# 467444_130_3_5-R1.net
KiCad netlist of a schematic drawn in Altium Designer
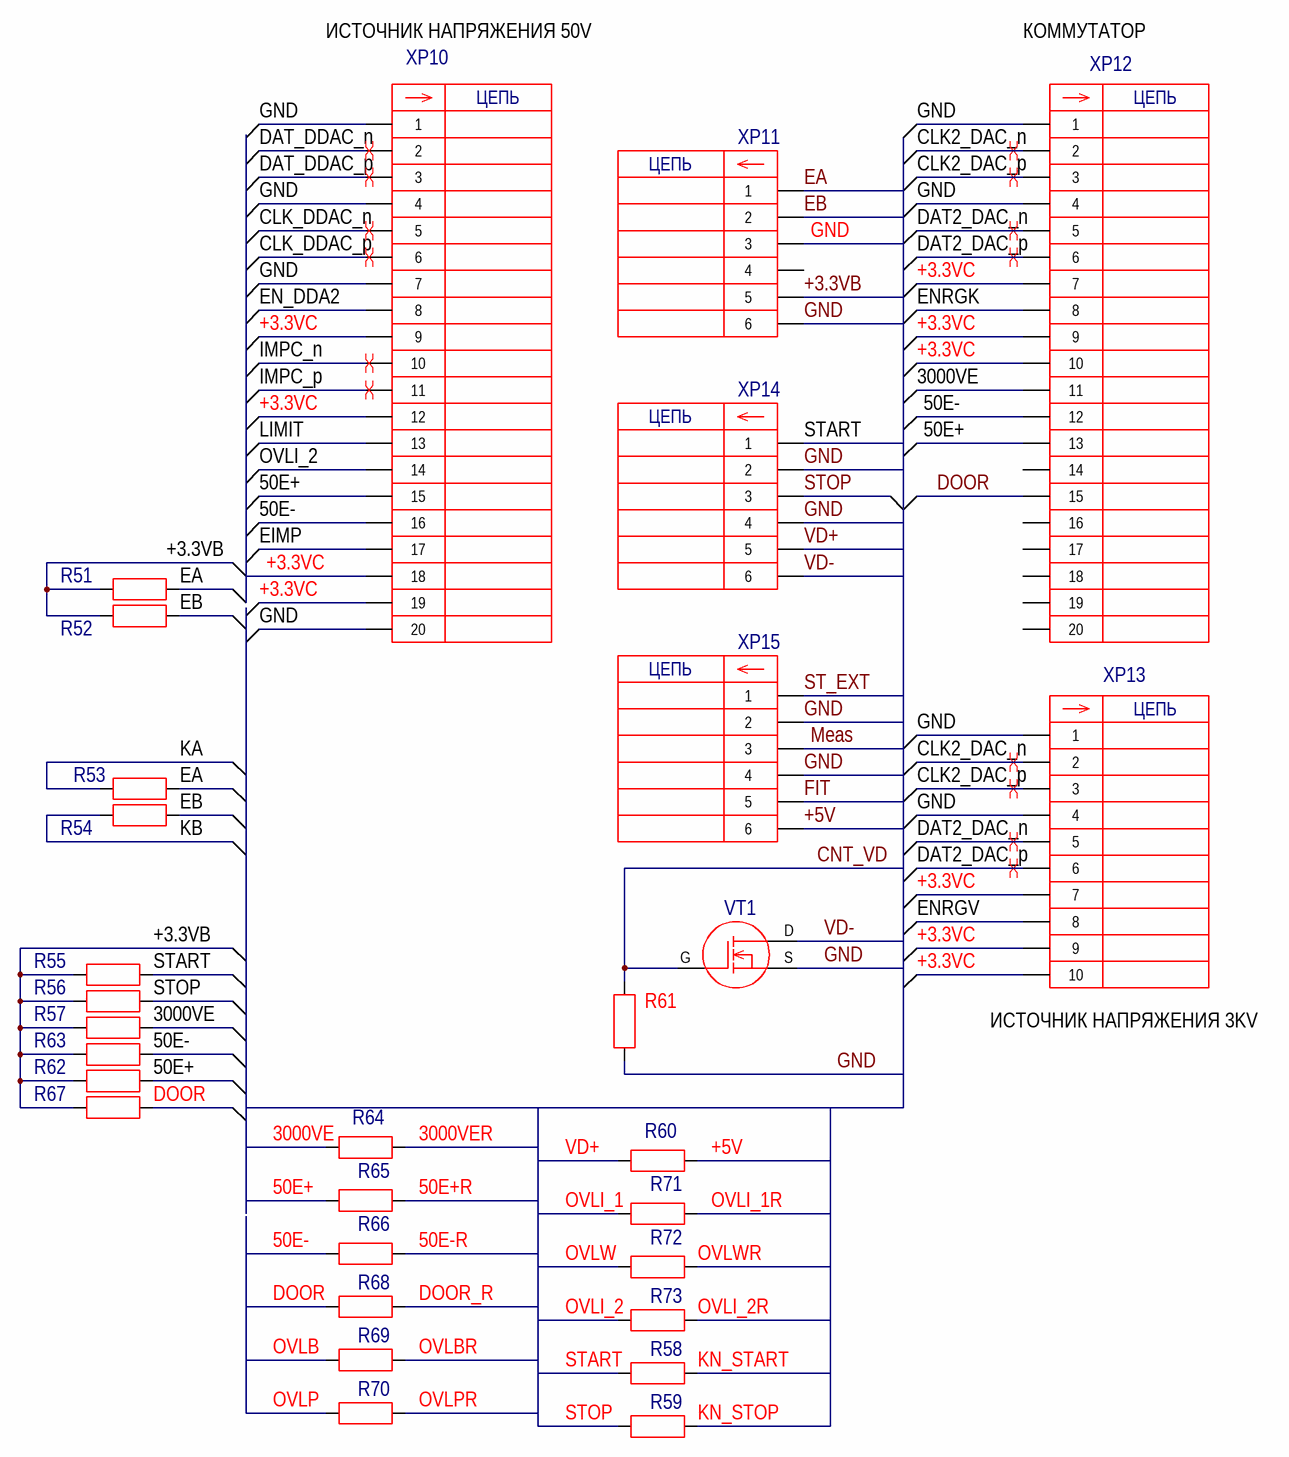
[diagram p0: УШЯИ.467444.130Э3_5-R1.SchDoc]

(export (version "E")
  (design (tool "Eeschema 10.0.6"))
  (components
    (comp (ref "R51")
      (value "5,1k")
      (footprint "R_0805 [2012 Metric]")
      (fields (field (name "TOLERANCE") "±5%"))
      (libsource (lib "lib") (part "R_Const"))
    )
    (comp (ref "R52")
      (value "5,1k")
      (footprint "R_0805 [2012 Metric]")
      (fields (field (name "TOLERANCE") "±5%"))
      (libsource (lib "lib") (part "R_Const"))
    )
    (comp (ref "R53")
      (value "1k")
      (footprint "R_0805 [2012 Metric]")
      (fields (field (name "TOLERANCE") "±5%"))
      (libsource (lib "lib") (part "R_Const"))
    )
    (comp (ref "R54")
      (value "1k")
      (footprint "R_0805 [2012 Metric]")
      (fields (field (name "TOLERANCE") "±5%"))
      (libsource (lib "lib") (part "R_Const"))
    )
    (comp (ref "R55")
      (value "5,1k")
      (footprint "R_0805 [2012 Metric]")
      (fields (field (name "TOLERANCE") "±5%"))
      (libsource (lib "lib") (part "R_Const"))
    )
    (comp (ref "R56")
      (value "5,1k")
      (footprint "R_0805 [2012 Metric]")
      (fields (field (name "TOLERANCE") "±5%"))
      (libsource (lib "lib") (part "R_Const"))
    )
    (comp (ref "R57")
      (value "10k")
      (footprint "R_0805 [2012 Metric]")
      (fields (field (name "TOLERANCE") "±1%"))
      (libsource (lib "lib") (part "R_Const"))
    )
    (comp (ref "R58")
      (value "~")
      (footprint "R_0805 [2012 Metric]")
      (fields (field (name "TOLERANCE") "±5%"))
      (libsource (lib "lib") (part "R_Const"))
    )
    (comp (ref "R59")
      (value "~")
      (footprint "R_0805 [2012 Metric]")
      (fields (field (name "TOLERANCE") "±5%"))
      (libsource (lib "lib") (part "R_Const"))
    )
    (comp (ref "R60")
      (value "150R")
      (footprint "R_0805 [2012 Metric]")
      (fields (field (name "TOLERANCE") "±5%"))
      (libsource (lib "lib") (part "R_Const"))
    )
    (comp (ref "R61")
      (value "10k")
      (footprint "R_0805 [2012 Metric]")
      (fields (field (name "TOLERANCE") "±5%"))
      (libsource (lib "lib") (part "R_Const"))
    )
    (comp (ref "R62")
      (value "3,6k")
      (footprint "R_0805 [2012 Metric]")
      (fields (field (name "TOLERANCE") "±5%"))
      (libsource (lib "lib") (part "R_Const"))
    )
    (comp (ref "R63")
      (value "3,6k")
      (footprint "R_0805 [2012 Metric]")
      (fields (field (name "TOLERANCE") "±5%"))
      (libsource (lib "lib") (part "R_Const"))
    )
    (comp (ref "R64")
      (value "1k")
      (footprint "R_0805 [2012 Metric]")
      (fields (field (name "TOLERANCE") "±5%"))
      (libsource (lib "lib") (part "R_Const"))
    )
    (comp (ref "R65")
      (value "1k")
      (footprint "R_0805 [2012 Metric]")
      (fields (field (name "TOLERANCE") "±5%"))
      (libsource (lib "lib") (part "R_Const"))
    )
    (comp (ref "R66")
      (value "1k")
      (footprint "R_0805 [2012 Metric]")
      (fields (field (name "TOLERANCE") "±5%"))
      (libsource (lib "lib") (part "R_Const"))
    )
    (comp (ref "R67")
      (value "1k")
      (footprint "R_0805 [2012 Metric]")
      (fields (field (name "TOLERANCE") "±5%"))
      (libsource (lib "lib") (part "R_Const"))
    )
    (comp (ref "R68")
      (value "1k")
      (footprint "R_0805 [2012 Metric]")
      (fields (field (name "TOLERANCE") "±5%"))
      (libsource (lib "lib") (part "R_Const"))
    )
    (comp (ref "R69")
      (value "1k")
      (footprint "R_0805 [2012 Metric]")
      (fields (field (name "TOLERANCE") "±5%"))
      (libsource (lib "lib") (part "R_Const"))
    )
    (comp (ref "R70")
      (value "1k")
      (footprint "R_0805 [2012 Metric]")
      (fields (field (name "TOLERANCE") "±5%"))
      (libsource (lib "lib") (part "R_Const"))
    )
    (comp (ref "R71")
      (value "1k")
      (footprint "R_0805 [2012 Metric]")
      (fields (field (name "TOLERANCE") "±5%"))
      (libsource (lib "lib") (part "R_Const"))
    )
    (comp (ref "R72")
      (value "1k")
      (footprint "R_0805 [2012 Metric]")
      (fields (field (name "TOLERANCE") "±5%"))
      (libsource (lib "lib") (part "R_Const"))
    )
    (comp (ref "R73")
      (value "1k")
      (footprint "R_0805 [2012 Metric]")
      (fields (field (name "TOLERANCE") "±5%"))
      (libsource (lib "lib") (part "R_Const"))
    )
    (comp (ref "VT1")
      (value "NDS7002A")
      (footprint "SOT-23-3_[TO-236AB]_Transistor_n")
      (description "Транзистор n-канальный, изолированный затвор")
      (fields (field (name "MANUFACTURER") "Onsemi"))
      (libsource (lib "lib") (part "n-channel"))
    )
    (comp (ref "XP10")
      (value "BH2-20R")
      (footprint "BH2-20R")
      (description "Male, 20 pins, 2 rows, Right Angle, DS1014-20RF1B-B, 2 mm")
      (fields (field (name "MANUFACTURER") "Connfly electronic"))
      (libsource (lib "lib") (part "M_20"))
    )
    (comp (ref "XP11")
      (value "AMPMODU II 280372-2")
      (footprint "AMP II-280372-2")
      (description "Male, 6 pin, 1 row, Vertical, Board-to-Board, 2.54 mm")
      (fields (field (name "MANUFACTURER") "TE Connectivity"))
      (libsource (lib "lib") (part "M_6"))
    )
    (comp (ref "XP12")
      (value "BH2-20R")
      (footprint "BH2-20R")
      (description "Male, 20 pins, 2 rows, Right Angle, DS1014-20RF1B-B, 2 mm")
      (fields (field (name "MANUFACTURER") "Connfly electronic"))
      (libsource (lib "lib") (part "M_20"))
    )
    (comp (ref "XP13")
      (value "BH2-10R")
      (footprint "BH2-10R")
      (description "Male, 10 pins, 2 rows, Vertical, DS1014-10RF1B-B, 2 mm")
      (fields (field (name "MANUFACTURER") "Connfly electronic"))
      (libsource (lib "lib") (part "M_10"))
    )
    (comp (ref "XP14")
      (value "AMPMODU II 280372-2")
      (footprint "AMP II-280372-2")
      (description "Male, 6 pin, 1 row, Vertical, Board-to-Board, 2.54 mm")
      (fields (field (name "MANUFACTURER") "TE Connectivity"))
      (libsource (lib "lib") (part "M_6"))
    )
    (comp (ref "XP15")
      (value "AMPMODU II 280372-2")
      (footprint "AMP II-280372-2")
      (description "Male, 6 pin, 1 row, Vertical, Board-to-Board, 2.54 mm")
      (fields (field (name "MANUFACTURER") "TE Connectivity"))
      (libsource (lib "lib") (part "M_6"))
    )
  )
  (nets
    (net (code "1") (name "/+3.3VB") (class "Default")
      (node (ref "R51") (pin "1") (pinfunction "1_1") (pintype "passive"))
      (node (ref "R52") (pin "1") (pinfunction "1_1") (pintype "passive"))
      (node (ref "R55") (pin "1") (pinfunction "1_1") (pintype "passive"))
      (node (ref "R56") (pin "1") (pinfunction "1_1") (pintype "passive"))
      (node (ref "R57") (pin "1") (pinfunction "1_1") (pintype "passive"))
      (node (ref "R62") (pin "1") (pinfunction "1_1") (pintype "passive"))
      (node (ref "R63") (pin "1") (pinfunction "1_1") (pintype "passive"))
      (node (ref "R67") (pin "1") (pinfunction "1_1") (pintype "passive"))
      (node (ref "XP11") (pin "5") (pinfunction "5_5") (pintype "passive"))
    )
    (net (code "2") (name "/+3.3VC") (class "Default")
      (node (ref "XP10") (pin "12") (pinfunction "12_12") (pintype "passive"))
      (node (ref "XP10") (pin "18") (pinfunction "18_18") (pintype "passive"))
      (node (ref "XP10") (pin "19") (pinfunction "19_19") (pintype "passive"))
      (node (ref "XP10") (pin "9") (pinfunction "9_9") (pintype "passive"))
      (node (ref "XP12") (pin "10") (pinfunction "10_10") (pintype "passive"))
      (node (ref "XP12") (pin "7") (pinfunction "7_7") (pintype "passive"))
      (node (ref "XP12") (pin "9") (pinfunction "9_9") (pintype "passive"))
      (node (ref "XP13") (pin "10") (pinfunction "10_10") (pintype "passive"))
      (node (ref "XP13") (pin "7") (pinfunction "7_7") (pintype "passive"))
      (node (ref "XP13") (pin "9") (pinfunction "9_9") (pintype "passive"))
    )
    (net (code "3") (name "/+5V") (class "Default")
      (node (ref "R60") (pin "2") (pinfunction "2_2") (pintype "passive"))
      (node (ref "XP15") (pin "6") (pinfunction "6_6") (pintype "passive"))
    )
    (net (code "4") (name "/50E+") (class "Default")
      (node (ref "R62") (pin "2") (pinfunction "2_2") (pintype "passive"))
      (node (ref "R65") (pin "1") (pinfunction "1_1") (pintype "passive"))
      (node (ref "XP10") (pin "15") (pinfunction "15_15") (pintype "passive"))
      (node (ref "XP12") (pin "13") (pinfunction "13_13") (pintype "passive"))
    )
    (net (code "5") (name "/50E+R") (class "Default")
      (node (ref "R65") (pin "2") (pinfunction "2_2") (pintype "passive"))
    )
    (net (code "6") (name "/50E-") (class "Default")
      (node (ref "R63") (pin "2") (pinfunction "2_2") (pintype "passive"))
      (node (ref "R66") (pin "1") (pinfunction "1_1") (pintype "passive"))
      (node (ref "XP10") (pin "16") (pinfunction "16_16") (pintype "passive"))
      (node (ref "XP12") (pin "12") (pinfunction "12_12") (pintype "passive"))
    )
    (net (code "7") (name "/50E-R") (class "Default")
      (node (ref "R66") (pin "2") (pinfunction "2_2") (pintype "passive"))
    )
    (net (code "8") (name "/3000VE") (class "Default")
      (node (ref "R57") (pin "2") (pinfunction "2_2") (pintype "passive"))
      (node (ref "R64") (pin "1") (pinfunction "1_1") (pintype "passive"))
      (node (ref "XP12") (pin "11") (pinfunction "11_11") (pintype "passive"))
    )
    (net (code "9") (name "/3000VER") (class "Default")
      (node (ref "R64") (pin "2") (pinfunction "2_2") (pintype "passive"))
    )
    (net (code "10") (name "/CLK2_DAC_n") (class "Default")
      (node (ref "XP12") (pin "2") (pinfunction "2_2") (pintype "passive"))
      (node (ref "XP13") (pin "2") (pinfunction "2_2") (pintype "passive"))
    )
    (net (code "11") (name "/CLK2_DAC_p") (class "Default")
      (node (ref "XP12") (pin "3") (pinfunction "3_3") (pintype "passive"))
      (node (ref "XP13") (pin "3") (pinfunction "3_3") (pintype "passive"))
    )
    (net (code "12") (name "/CLK_DDAC_n") (class "Default")
      (node (ref "XP10") (pin "5") (pinfunction "5_5") (pintype "passive"))
    )
    (net (code "13") (name "/CLK_DDAC_p") (class "Default")
      (node (ref "XP10") (pin "6") (pinfunction "6_6") (pintype "passive"))
    )
    (net (code "14") (name "/CNT_VD") (class "Default")
      (node (ref "R61") (pin "2") (pinfunction "2_2") (pintype "passive"))
      (node (ref "VT1") (pin "G") (pinfunction "З_G") (pintype "passive"))
    )
    (net (code "15") (name "/DAT2_DAC_n") (class "Default")
      (node (ref "XP12") (pin "5") (pinfunction "5_5") (pintype "passive"))
      (node (ref "XP13") (pin "5") (pinfunction "5_5") (pintype "passive"))
    )
    (net (code "16") (name "/DAT2_DAC_p") (class "Default")
      (node (ref "XP12") (pin "6") (pinfunction "6_6") (pintype "passive"))
      (node (ref "XP13") (pin "6") (pinfunction "6_6") (pintype "passive"))
    )
    (net (code "17") (name "/DAT_DDAC_n") (class "Default")
      (node (ref "XP10") (pin "2") (pinfunction "2_2") (pintype "passive"))
    )
    (net (code "18") (name "/DAT_DDAC_p") (class "Default")
      (node (ref "XP10") (pin "3") (pinfunction "3_3") (pintype "passive"))
    )
    (net (code "19") (name "/DOOR") (class "Default")
      (node (ref "R67") (pin "2") (pinfunction "2_2") (pintype "passive"))
      (node (ref "R68") (pin "1") (pinfunction "1_1") (pintype "passive"))
      (node (ref "XP12") (pin "15") (pinfunction "15_15") (pintype "passive"))
    )
    (net (code "20") (name "/DOOR_R") (class "Default")
      (node (ref "R68") (pin "2") (pinfunction "2_2") (pintype "passive"))
    )
    (net (code "21") (name "/EA") (class "Default")
      (node (ref "R51") (pin "2") (pinfunction "2_2") (pintype "passive"))
      (node (ref "R53") (pin "2") (pinfunction "2_2") (pintype "passive"))
      (node (ref "XP11") (pin "1") (pinfunction "1_1") (pintype "passive"))
    )
    (net (code "22") (name "/EB") (class "Default")
      (node (ref "R52") (pin "2") (pinfunction "2_2") (pintype "passive"))
      (node (ref "R54") (pin "2") (pinfunction "2_2") (pintype "passive"))
      (node (ref "XP11") (pin "2") (pinfunction "2_2") (pintype "passive"))
    )
    (net (code "23") (name "/EIMP") (class "Default")
      (node (ref "XP10") (pin "17") (pinfunction "17_17") (pintype "passive"))
    )
    (net (code "24") (name "/ENRGK") (class "Default")
      (node (ref "XP12") (pin "8") (pinfunction "8_8") (pintype "passive"))
    )
    (net (code "25") (name "/ENRGV") (class "Default")
      (node (ref "XP13") (pin "8") (pinfunction "8_8") (pintype "passive"))
    )
    (net (code "26") (name "/EN_DDA2") (class "Default")
      (node (ref "XP10") (pin "8") (pinfunction "8_8") (pintype "passive"))
    )
    (net (code "27") (name "/FIT") (class "Default")
      (node (ref "XP15") (pin "5") (pinfunction "5_5") (pintype "passive"))
    )
    (net (code "28") (name "/GND") (class "Default")
      (node (ref "R61") (pin "1") (pinfunction "1_1") (pintype "passive"))
      (node (ref "VT1") (pin "S") (pinfunction "И_S") (pintype "passive"))
      (node (ref "XP10") (pin "1") (pinfunction "1_1") (pintype "passive"))
      (node (ref "XP10") (pin "20") (pinfunction "20_20") (pintype "passive"))
      (node (ref "XP10") (pin "4") (pinfunction "4_4") (pintype "passive"))
      (node (ref "XP10") (pin "7") (pinfunction "7_7") (pintype "passive"))
      (node (ref "XP11") (pin "3") (pinfunction "3_3") (pintype "passive"))
      (node (ref "XP11") (pin "6") (pinfunction "6_6") (pintype "passive"))
      (node (ref "XP12") (pin "1") (pinfunction "1_1") (pintype "passive"))
      (node (ref "XP12") (pin "4") (pinfunction "4_4") (pintype "passive"))
      (node (ref "XP13") (pin "1") (pinfunction "1_1") (pintype "passive"))
      (node (ref "XP13") (pin "4") (pinfunction "4_4") (pintype "passive"))
      (node (ref "XP14") (pin "2") (pinfunction "2_2") (pintype "passive"))
      (node (ref "XP14") (pin "4") (pinfunction "4_4") (pintype "passive"))
      (node (ref "XP15") (pin "2") (pinfunction "2_2") (pintype "passive"))
      (node (ref "XP15") (pin "4") (pinfunction "4_4") (pintype "passive"))
    )
    (net (code "29") (name "/IMPC_n") (class "Default")
      (node (ref "XP10") (pin "10") (pinfunction "10_10") (pintype "passive"))
    )
    (net (code "30") (name "/IMPC_p") (class "Default")
      (node (ref "XP10") (pin "11") (pinfunction "11_11") (pintype "passive"))
    )
    (net (code "31") (name "/KA") (class "Default")
      (node (ref "R53") (pin "1") (pinfunction "1_1") (pintype "passive"))
    )
    (net (code "32") (name "/KB") (class "Default")
      (node (ref "R54") (pin "1") (pinfunction "1_1") (pintype "passive"))
    )
    (net (code "33") (name "/KN_START") (class "Default")
      (node (ref "R58") (pin "2") (pinfunction "2_2") (pintype "passive"))
    )
    (net (code "34") (name "/KN_STOP") (class "Default")
      (node (ref "R59") (pin "2") (pinfunction "2_2") (pintype "passive"))
    )
    (net (code "35") (name "/LIMIT") (class "Default")
      (node (ref "XP10") (pin "13") (pinfunction "13_13") (pintype "passive"))
    )
    (net (code "36") (name "/Meas") (class "Default")
      (node (ref "XP15") (pin "3") (pinfunction "3_3") (pintype "passive"))
    )
    (net (code "37") (name "/OVLB") (class "Default")
      (node (ref "R69") (pin "1") (pinfunction "1_1") (pintype "passive"))
    )
    (net (code "38") (name "/OVLBR") (class "Default")
      (node (ref "R69") (pin "2") (pinfunction "2_2") (pintype "passive"))
    )
    (net (code "39") (name "/OVLI_1") (class "Default")
      (node (ref "R71") (pin "1") (pinfunction "1_1") (pintype "passive"))
    )
    (net (code "40") (name "/OVLI_1R") (class "Default")
      (node (ref "R71") (pin "2") (pinfunction "2_2") (pintype "passive"))
    )
    (net (code "41") (name "/OVLI_2") (class "Default")
      (node (ref "R73") (pin "1") (pinfunction "1_1") (pintype "passive"))
      (node (ref "XP10") (pin "14") (pinfunction "14_14") (pintype "passive"))
    )
    (net (code "42") (name "/OVLI_2R") (class "Default")
      (node (ref "R73") (pin "2") (pinfunction "2_2") (pintype "passive"))
    )
    (net (code "43") (name "/OVLP") (class "Default")
      (node (ref "R70") (pin "1") (pinfunction "1_1") (pintype "passive"))
    )
    (net (code "44") (name "/OVLPR") (class "Default")
      (node (ref "R70") (pin "2") (pinfunction "2_2") (pintype "passive"))
    )
    (net (code "45") (name "/OVLW") (class "Default")
      (node (ref "R72") (pin "1") (pinfunction "1_1") (pintype "passive"))
    )
    (net (code "46") (name "/OVLWR") (class "Default")
      (node (ref "R72") (pin "2") (pinfunction "2_2") (pintype "passive"))
    )
    (net (code "47") (name "/START") (class "Default")
      (node (ref "R55") (pin "2") (pinfunction "2_2") (pintype "passive"))
      (node (ref "R58") (pin "1") (pinfunction "1_1") (pintype "passive"))
      (node (ref "XP14") (pin "1") (pinfunction "1_1") (pintype "passive"))
    )
    (net (code "48") (name "/STOP") (class "Default")
      (node (ref "R56") (pin "2") (pinfunction "2_2") (pintype "passive"))
      (node (ref "R59") (pin "1") (pinfunction "1_1") (pintype "passive"))
      (node (ref "XP14") (pin "3") (pinfunction "3_3") (pintype "passive"))
    )
    (net (code "49") (name "/ST_EXT") (class "Default")
      (node (ref "XP15") (pin "1") (pinfunction "1_1") (pintype "passive"))
    )
    (net (code "50") (name "/VD+") (class "Default")
      (node (ref "R60") (pin "1") (pinfunction "1_1") (pintype "passive"))
      (node (ref "XP14") (pin "5") (pinfunction "5_5") (pintype "passive"))
    )
    (net (code "51") (name "/VD-") (class "Default")
      (node (ref "VT1") (pin "D") (pinfunction "C_D") (pintype "passive"))
      (node (ref "XP14") (pin "6") (pinfunction "6_6") (pintype "passive"))
    )
    (net (code "52") (name "unconnected-(XP11-Pad4)") (class "Default")
      (node (ref "XP11") (pin "4") (pinfunction "4_4") (pintype "passive"))
    )
    (net (code "53") (name "unconnected-(XP12-Pad14)") (class "Default")
      (node (ref "XP12") (pin "14") (pinfunction "14_14") (pintype "passive"))
    )
    (net (code "54") (name "unconnected-(XP12-Pad16)") (class "Default")
      (node (ref "XP12") (pin "16") (pinfunction "16_16") (pintype "passive"))
    )
    (net (code "55") (name "unconnected-(XP12-Pad17)") (class "Default")
      (node (ref "XP12") (pin "17") (pinfunction "17_17") (pintype "passive"))
    )
    (net (code "56") (name "unconnected-(XP12-Pad18)") (class "Default")
      (node (ref "XP12") (pin "18") (pinfunction "18_18") (pintype "passive"))
    )
    (net (code "57") (name "unconnected-(XP12-Pad19)") (class "Default")
      (node (ref "XP12") (pin "19") (pinfunction "19_19") (pintype "passive"))
    )
    (net (code "58") (name "unconnected-(XP12-Pad20)") (class "Default")
      (node (ref "XP12") (pin "20") (pinfunction "20_20") (pintype "passive"))
    )
  )
)
